# 2.net
KiCad netlist of a schematic drawn in EAGLE
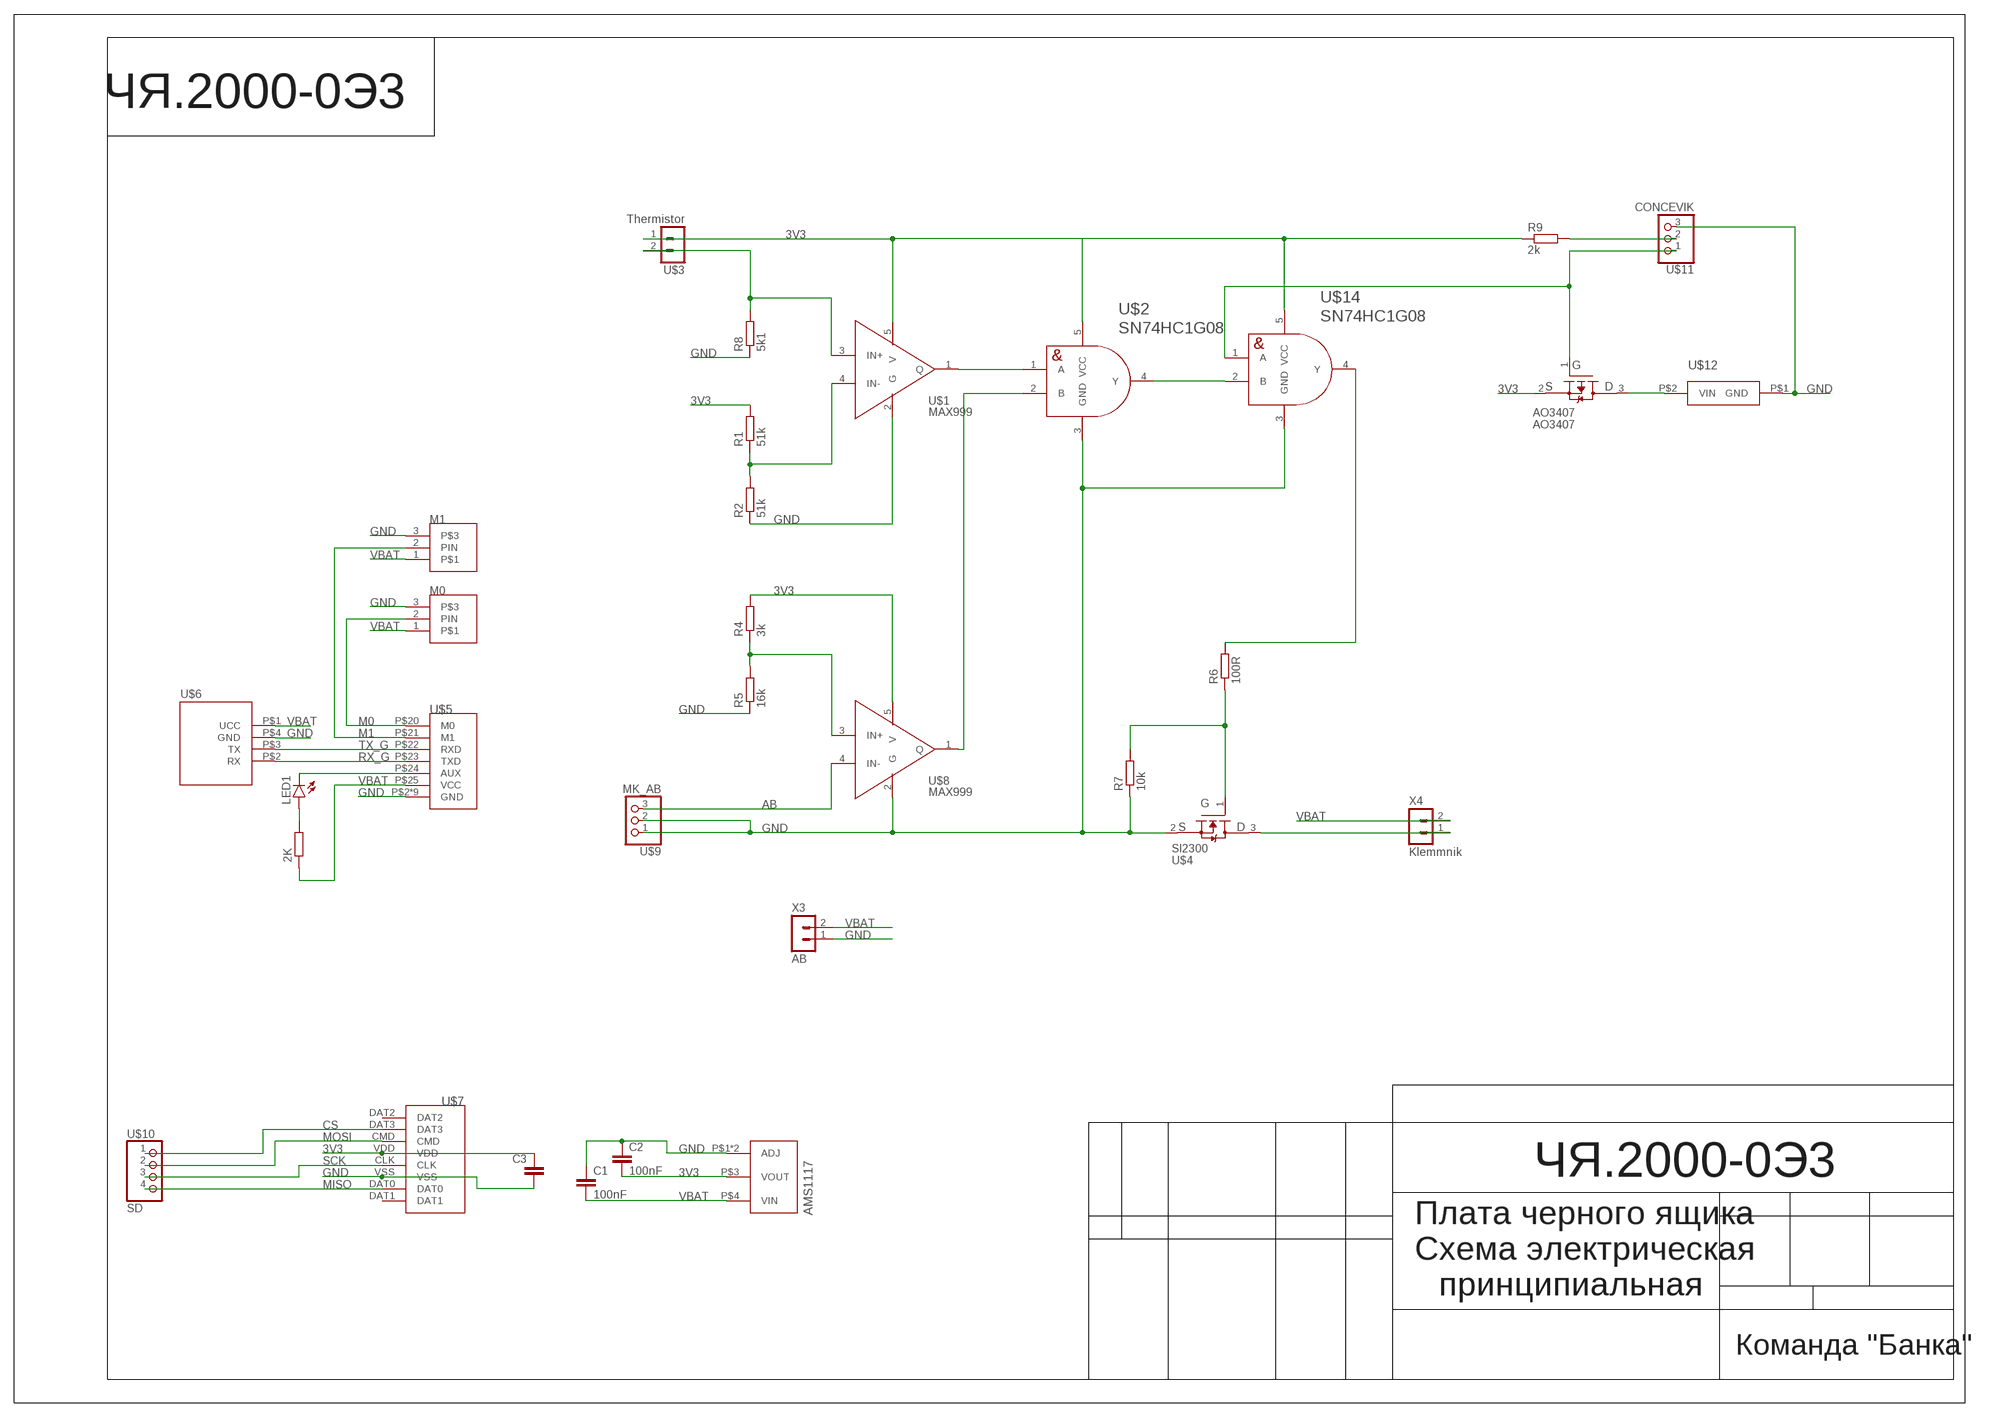
[diagram p0: schematic, sheet 1]

(export (version "E")
  (design (tool "Eeschema 10.0.6"))
  (components
    (comp (ref "2K")
      (value "R-EU_R0603")
      (footprint "eagle-import:R0603")
      (libsource (lib "eagle-import") (part "R-EU_R0603"))
    )
    (comp (ref "AMS1117")
      (value "AMS1117")
      (footprint "eagle-import:SOT223")
      (libsource (lib "eagle-import") (part "AMS1117"))
    )
    (comp (ref "AO3407")
      (value "AO3407")
      (footprint "eagle-import:SOT23-3")
      (libsource (lib "eagle-import") (part "AO3407"))
    )
    (comp (ref "C1")
      (value "100nF")
      (footprint "eagle-import:C0603")
      (libsource (lib "eagle-import") (part "C-EUC0603"))
    )
    (comp (ref "C2")
      (value "100nF")
      (footprint "eagle-import:C0603")
      (libsource (lib "eagle-import") (part "C-EUC0603"))
    )
    (comp (ref "C3")
      (value "C-EUC0603")
      (footprint "eagle-import:C0603")
      (libsource (lib "eagle-import") (part "C-EUC0603"))
    )
    (comp (ref "LED1")
      (value "LEDCHIP-LED0603")
      (footprint "eagle-import:CHIP-LED0603")
      (libsource (lib "eagle-import") (part "LEDCHIP-LED0603"))
    )
    (comp (ref "M0")
      (value "CONNECT_3")
      (footprint "eagle-import:CONNECT_3")
      (libsource (lib "eagle-import") (part "CONNECT_3"))
    )
    (comp (ref "M1")
      (value "CONNECT_3")
      (footprint "eagle-import:CONNECT_3")
      (libsource (lib "eagle-import") (part "CONNECT_3"))
    )
    (comp (ref "R1")
      (value "51k")
      (footprint "eagle-import:R0603")
      (libsource (lib "eagle-import") (part "R-EU_R0603"))
    )
    (comp (ref "R2")
      (value "51k")
      (footprint "eagle-import:R0603")
      (libsource (lib "eagle-import") (part "R-EU_R0603"))
    )
    (comp (ref "R4")
      (value "3k")
      (footprint "eagle-import:R0603")
      (libsource (lib "eagle-import") (part "R-EU_R0603"))
    )
    (comp (ref "R5")
      (value "16k")
      (footprint "eagle-import:R0603")
      (libsource (lib "eagle-import") (part "R-EU_R0603"))
    )
    (comp (ref "R6")
      (value "100R")
      (footprint "eagle-import:R0603")
      (libsource (lib "eagle-import") (part "R-EU_R0603"))
    )
    (comp (ref "R7")
      (value "10k")
      (footprint "eagle-import:R0603")
      (libsource (lib "eagle-import") (part "R-EU_R0603"))
    )
    (comp (ref "R8")
      (value "5k1")
      (footprint "eagle-import:R0603")
      (libsource (lib "eagle-import") (part "R-EU_R0603"))
    )
    (comp (ref "R9")
      (value "2k")
      (footprint "eagle-import:R0603")
      (libsource (lib "eagle-import") (part "R-EU_R0603"))
    )
    (comp (ref "U$1")
      (value "MAX999")
      (footprint "eagle-import:SOT23-5")
      (libsource (lib "eagle-import") (part "MAX999"))
    )
    (comp (ref "U$2")
      (value "SN74HC1G08")
      (footprint "eagle-import:SOT23-5")
      (libsource (lib "eagle-import") (part "SN74HC1G08"))
    )
    (comp (ref "U$3")
      (value "Thermistor")
      (footprint "eagle-import:53047-02")
      (libsource (lib "eagle-import") (part "MOLEX-2-1.25"))
    )
    (comp (ref "U$4")
      (value "SI2300")
      (footprint "eagle-import:SOT23-3")
      (libsource (lib "eagle-import") (part "SI2300"))
    )
    (comp (ref "U$5")
      (value "E220-400T22S")
      (footprint "eagle-import:E220-400T22S")
      (libsource (lib "eagle-import") (part "E220-400T22S"))
    )
    (comp (ref "U$6")
      (value "GPS-NEO7M")
      (footprint "eagle-import:GPS-NEO7M")
      (libsource (lib "eagle-import") (part "GPS-NEO7M"))
    )
    (comp (ref "U$7") (value "SD") (footprint "eagle-import:SD") (libsource (lib "eagle-import") (part "SD")))
    (comp (ref "U$8")
      (value "MAX999")
      (footprint "eagle-import:SOT23-5")
      (libsource (lib "eagle-import") (part "MAX999"))
    )
    (comp (ref "U$9")
      (value "MK_AB")
      (footprint "eagle-import:53047-03")
      (libsource (lib "eagle-import") (part "MOLEX-3-1.25"))
    )
    (comp (ref "U$10")
      (value "SD")
      (footprint "eagle-import:53047-04")
      (libsource (lib "eagle-import") (part "MOLEX-4-1.25"))
    )
    (comp (ref "U$11")
      (value "CONCEVIK")
      (footprint "eagle-import:53047-03")
      (libsource (lib "eagle-import") (part "MOLEX-3-1.25"))
    )
    (comp (ref "U$12")
      (value "BUZZERS8R6")
      (footprint "eagle-import:BUZZER-S8R12")
      (libsource (lib "eagle-import") (part "BUZZERS8R6"))
    )
    (comp (ref "U$14")
      (value "SN74HC1G08")
      (footprint "eagle-import:SOT23-5")
      (libsource (lib "eagle-import") (part "SN74HC1G08"))
    )
    (comp (ref "X3")
      (value "AB")
      (footprint "eagle-import:JST-2-2.5")
      (libsource (lib "eagle-import") (part "JST-2-2.5"))
    )
    (comp (ref "X4")
      (value "Klemmnik")
      (footprint "eagle-import:JST-2-2.5")
      (libsource (lib "eagle-import") (part "JST-2-2.5"))
    )
  )
  (nets
    (net (code "1") (name "/3V3") (class "Default")
      (node (ref "AMS1117") (pin "P$3") (pinfunction "VOUT_P$3") (pintype "bidirectional"))
      (node (ref "AO3407") (pin "2") (pinfunction "PS_2") (pintype "passive"))
      (node (ref "C2") (pin "2") (pinfunction "2_2") (pintype "passive"))
      (node (ref "C3") (pin "1") (pinfunction "1_1") (pintype "passive"))
      (node (ref "R1") (pin "2") (pinfunction "2_2") (pintype "passive"))
      (node (ref "R4") (pin "2") (pinfunction "2_2") (pintype "passive"))
      (node (ref "R9") (pin "2") (pinfunction "2_2") (pintype "passive"))
      (node (ref "U$1") (pin "5") (pinfunction "V_5") (pintype "bidirectional"))
      (node (ref "U$14") (pin "5") (pinfunction "VCC_5") (pintype "bidirectional"))
      (node (ref "U$2") (pin "5") (pinfunction "VCC_5") (pintype "bidirectional"))
      (node (ref "U$3") (pin "1") (pinfunction "1_1") (pintype "passive"))
      (node (ref "U$7") (pin "VDD") (pinfunction "VDD_VDD") (pintype "bidirectional"))
      (node (ref "U$8") (pin "5") (pinfunction "V_5") (pintype "bidirectional"))
    )
    (net (code "2") (name "/AB") (class "Default")
      (node (ref "U$8") (pin "4") (pinfunction "IN-_4") (pintype "bidirectional"))
      (node (ref "U$9") (pin "3") (pinfunction "3_3") (pintype "passive"))
    )
    (net (code "3") (name "/CS") (class "Default")
      (node (ref "U$10") (pin "1") (pinfunction "1_1") (pintype "passive"))
      (node (ref "U$7") (pin "DAT3") (pinfunction "DAT3_DAT3") (pintype "bidirectional"))
    )
    (net (code "4") (name "/GND") (class "Default")
      (node (ref "AMS1117") (pin "P$1") (pinfunction "ADJ_P$1") (pintype "bidirectional"))
      (node (ref "AMS1117") (pin "P$2") (pinfunction "ADJ_P$2") (pintype "bidirectional"))
      (node (ref "C1") (pin "1") (pinfunction "1_1") (pintype "passive"))
      (node (ref "C2") (pin "1") (pinfunction "1_1") (pintype "passive"))
      (node (ref "C3") (pin "2") (pinfunction "2_2") (pintype "passive"))
      (node (ref "M0") (pin "3") (pinfunction "P$3_3") (pintype "bidirectional"))
      (node (ref "M1") (pin "3") (pinfunction "P$3_3") (pintype "bidirectional"))
      (node (ref "R2") (pin "1") (pinfunction "1_1") (pintype "passive"))
      (node (ref "R5") (pin "1") (pinfunction "1_1") (pintype "passive"))
      (node (ref "R7") (pin "1") (pinfunction "1_1") (pintype "passive"))
      (node (ref "R8") (pin "1") (pinfunction "1_1") (pintype "passive"))
      (node (ref "U$1") (pin "2") (pinfunction "G_2") (pintype "bidirectional"))
      (node (ref "U$11") (pin "3") (pinfunction "3_3") (pintype "passive"))
      (node (ref "U$12") (pin "P$1") (pinfunction "GND_P$1") (pintype "bidirectional"))
      (node (ref "U$14") (pin "3") (pinfunction "GND_3") (pintype "bidirectional"))
      (node (ref "U$2") (pin "3") (pinfunction "GND_3") (pintype "bidirectional"))
      (node (ref "U$4") (pin "2") (pinfunction "NS_2") (pintype "passive"))
      (node (ref "U$5") (pin "P$11") (pinfunction "GND_P$11") (pintype "bidirectional"))
      (node (ref "U$5") (pin "P$13") (pinfunction "GND_P$13") (pintype "bidirectional"))
      (node (ref "U$5") (pin "P$14") (pinfunction "GND_P$14") (pintype "bidirectional"))
      (node (ref "U$5") (pin "P$15") (pinfunction "GND_P$15") (pintype "bidirectional"))
      (node (ref "U$5") (pin "P$16") (pinfunction "GND_P$16") (pintype "bidirectional"))
      (node (ref "U$5") (pin "P$19") (pinfunction "GND_P$19") (pintype "bidirectional"))
      (node (ref "U$5") (pin "P$2") (pinfunction "GND_P$2") (pintype "bidirectional"))
      (node (ref "U$5") (pin "P$26") (pinfunction "GND_P$26") (pintype "bidirectional"))
      (node (ref "U$5") (pin "P$8") (pinfunction "GND_P$8") (pintype "bidirectional"))
      (node (ref "U$6") (pin "P$4") (pinfunction "GND_P$4") (pintype "bidirectional"))
      (node (ref "U$7") (pin "VSS") (pinfunction "VSS_VSS") (pintype "bidirectional"))
      (node (ref "U$8") (pin "2") (pinfunction "G_2") (pintype "bidirectional"))
      (node (ref "U$9") (pin "1") (pinfunction "1_1") (pintype "passive"))
      (node (ref "U$9") (pin "2") (pinfunction "2_2") (pintype "passive"))
      (node (ref "X3") (pin "1") (pinfunction "1_1") (pintype "passive"))
    )
    (net (code "5") (name "/M0") (class "Default")
      (node (ref "M0") (pin "2") (pinfunction "PIN_2") (pintype "bidirectional"))
      (node (ref "U$5") (pin "P$20") (pinfunction "M0_P$20") (pintype "bidirectional"))
    )
    (net (code "6") (name "/M1") (class "Default")
      (node (ref "M1") (pin "2") (pinfunction "PIN_2") (pintype "bidirectional"))
      (node (ref "U$5") (pin "P$21") (pinfunction "M1_P$21") (pintype "bidirectional"))
    )
    (net (code "7") (name "/MISO") (class "Default")
      (node (ref "U$10") (pin "4") (pinfunction "4_4") (pintype "passive"))
      (node (ref "U$7") (pin "DAT0") (pinfunction "DAT0_DAT0") (pintype "bidirectional"))
    )
    (net (code "8") (name "/MOSI") (class "Default")
      (node (ref "U$10") (pin "2") (pinfunction "2_2") (pintype "passive"))
      (node (ref "U$7") (pin "CMD") (pinfunction "CMD_CMD") (pintype "bidirectional"))
    )
    (net (code "9") (name "/RX_G") (class "Default")
      (node (ref "U$5") (pin "P$23") (pinfunction "TXD_P$23") (pintype "bidirectional"))
      (node (ref "U$6") (pin "P$2") (pinfunction "RX_P$2") (pintype "bidirectional"))
    )
    (net (code "10") (name "/SCK") (class "Default")
      (node (ref "U$10") (pin "3") (pinfunction "3_3") (pintype "passive"))
      (node (ref "U$7") (pin "CLK") (pinfunction "CLK_CLK") (pintype "bidirectional"))
    )
    (net (code "11") (name "/TX_G") (class "Default")
      (node (ref "U$5") (pin "P$22") (pinfunction "RXD_P$22") (pintype "bidirectional"))
      (node (ref "U$6") (pin "P$3") (pinfunction "TX_P$3") (pintype "bidirectional"))
    )
    (net (code "12") (name "/VBAT") (class "Default")
      (node (ref "2K") (pin "1") (pinfunction "1_1") (pintype "passive"))
      (node (ref "AMS1117") (pin "P$4") (pinfunction "VIN_P$4") (pintype "bidirectional"))
      (node (ref "C1") (pin "2") (pinfunction "2_2") (pintype "passive"))
      (node (ref "M0") (pin "1") (pinfunction "P$1_1") (pintype "bidirectional"))
      (node (ref "M1") (pin "1") (pinfunction "P$1_1") (pintype "bidirectional"))
      (node (ref "U$5") (pin "P$25") (pinfunction "VCC_P$25") (pintype "bidirectional"))
      (node (ref "U$6") (pin "P$1") (pinfunction "UCC_P$1") (pintype "bidirectional"))
      (node (ref "X3") (pin "2") (pinfunction "2_2") (pintype "passive"))
      (node (ref "X4") (pin "2") (pinfunction "2_2") (pintype "passive"))
    )
    (net (code "13") (name "Net-(2K-Pad2)") (class "Default")
      (node (ref "2K") (pin "2") (pinfunction "2_2") (pintype "passive"))
      (node (ref "LED1") (pin "A") (pinfunction "A_A") (pintype "passive"))
    )
    (net (code "14") (name "Net-(AO3407-PD)") (class "Default")
      (node (ref "AO3407") (pin "3") (pinfunction "PD_3") (pintype "passive"))
      (node (ref "U$12") (pin "P$2") (pinfunction "VIN_P$2") (pintype "bidirectional"))
    )
    (net (code "15") (name "Net-(AO3407-PG)") (class "Default")
      (node (ref "AO3407") (pin "1") (pinfunction "PG_1") (pintype "passive"))
      (node (ref "U$11") (pin "1") (pinfunction "1_1") (pintype "passive"))
      (node (ref "U$14") (pin "1") (pinfunction "A_1") (pintype "bidirectional"))
    )
    (net (code "16") (name "Net-(R9-Pad1)") (class "Default")
      (node (ref "R9") (pin "1") (pinfunction "1_1") (pintype "passive"))
      (node (ref "U$11") (pin "2") (pinfunction "2_2") (pintype "passive"))
    )
    (net (code "17") (name "Net-(U$1-IN+)") (class "Default")
      (node (ref "R8") (pin "2") (pinfunction "2_2") (pintype "passive"))
      (node (ref "U$1") (pin "3") (pinfunction "IN+_3") (pintype "bidirectional"))
      (node (ref "U$3") (pin "2") (pinfunction "2_2") (pintype "passive"))
    )
    (net (code "18") (name "Net-(U$1-IN-)") (class "Default")
      (node (ref "R1") (pin "1") (pinfunction "1_1") (pintype "passive"))
      (node (ref "R2") (pin "2") (pinfunction "2_2") (pintype "passive"))
      (node (ref "U$1") (pin "4") (pinfunction "IN-_4") (pintype "bidirectional"))
    )
    (net (code "19") (name "Net-(U$1-Q)") (class "Default")
      (node (ref "U$1") (pin "1") (pinfunction "Q_1") (pintype "bidirectional"))
      (node (ref "U$2") (pin "1") (pinfunction "A_1") (pintype "bidirectional"))
    )
    (net (code "20") (name "Net-(U$2-B)") (class "Default")
      (node (ref "U$2") (pin "2") (pinfunction "B_2") (pintype "bidirectional"))
      (node (ref "U$8") (pin "1") (pinfunction "Q_1") (pintype "bidirectional"))
    )
    (net (code "21") (name "Net-(U$4-ND)") (class "Default")
      (node (ref "U$4") (pin "3") (pinfunction "ND_3") (pintype "passive"))
      (node (ref "X4") (pin "1") (pinfunction "1_1") (pintype "passive"))
    )
    (net (code "22") (name "Net-(U$4-NG)") (class "Default")
      (node (ref "R6") (pin "1") (pinfunction "1_1") (pintype "passive"))
      (node (ref "R7") (pin "2") (pinfunction "2_2") (pintype "passive"))
      (node (ref "U$4") (pin "1") (pinfunction "NG_1") (pintype "passive"))
    )
    (net (code "23") (name "Net-(U$5-AUX)") (class "Default")
      (node (ref "LED1") (pin "C") (pinfunction "C_C") (pintype "passive"))
      (node (ref "U$5") (pin "P$24") (pinfunction "AUX_P$24") (pintype "bidirectional"))
    )
    (net (code "24") (name "Net-(U$8-IN+)") (class "Default")
      (node (ref "R4") (pin "1") (pinfunction "1_1") (pintype "passive"))
      (node (ref "R5") (pin "2") (pinfunction "2_2") (pintype "passive"))
      (node (ref "U$8") (pin "3") (pinfunction "IN+_3") (pintype "bidirectional"))
    )
    (net (code "25") (name "Net-(U$14-B)") (class "Default")
      (node (ref "U$14") (pin "2") (pinfunction "B_2") (pintype "bidirectional"))
      (node (ref "U$2") (pin "4") (pinfunction "Y_4") (pintype "bidirectional"))
    )
    (net (code "26") (name "Net-(U$14-Y)") (class "Default")
      (node (ref "R6") (pin "2") (pinfunction "2_2") (pintype "passive"))
      (node (ref "U$14") (pin "4") (pinfunction "Y_4") (pintype "bidirectional"))
    )
    (net (code "27") (name "unconnected-(U$7-PadDAT1)") (class "Default")
      (node (ref "U$7") (pin "DAT1") (pinfunction "DAT1_DAT1") (pintype "bidirectional"))
    )
    (net (code "28") (name "unconnected-(U$7-PadDAT2)") (class "Default")
      (node (ref "U$7") (pin "DAT2") (pinfunction "DAT2_DAT2") (pintype "bidirectional"))
    )
  )
)
